# Camera.net
KiCad netlist of a schematic drawn in Altium Designer
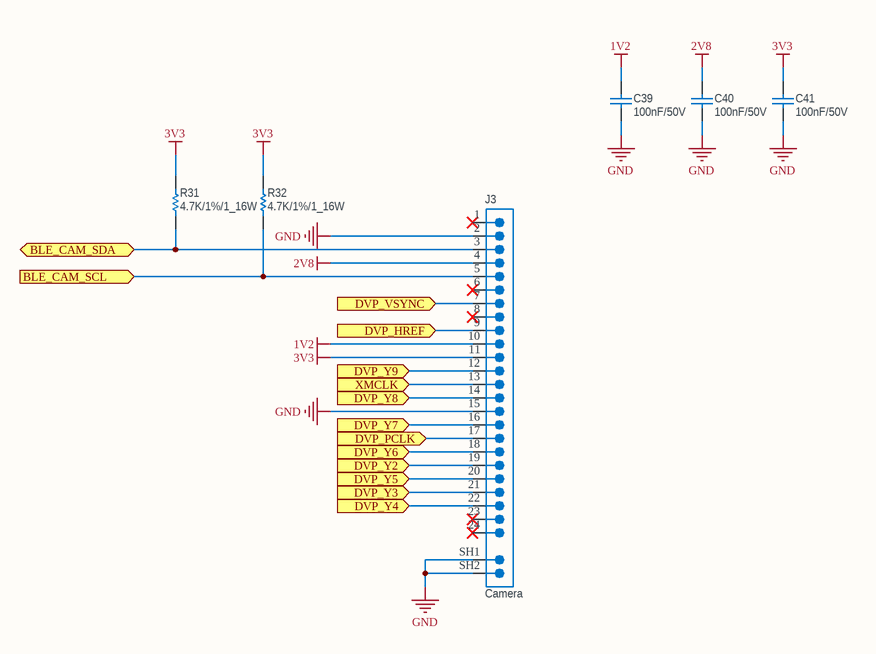
[diagram p0: Camera.SchDoc]

(export (version "E")
  (design (tool "Eeschema 10.0.6"))
  (components
    (comp (ref "C39")
      (value "100nF/50V")
      (footprint "CAP_0402")
      (description "CAP, size 0402, 100nF, 50V")
      (fields (field (name "SUPPLY PART NUMBER") "Tụ Gốm 0402 100nF (0.1uF) 50V"))
      (libsource (lib "BluetoothTracking") (part "Ceramic_Cap_100nF_50V_0402"))
    )
    (comp (ref "C40")
      (value "100nF/50V")
      (footprint "CAP_0402")
      (description "CAP, size 0402, 100nF, 50V")
      (fields (field (name "SUPPLY PART NUMBER") "Tụ Gốm 0402 100nF (0.1uF) 50V"))
      (libsource (lib "BluetoothTracking") (part "Ceramic_Cap_100nF_50V_0402"))
    )
    (comp (ref "C41")
      (value "100nF/50V")
      (footprint "CAP_0402")
      (description "CAP, size 0402, 100nF, 50V")
      (fields (field (name "SUPPLY PART NUMBER") "Tụ Gốm 0402 100nF (0.1uF) 50V"))
      (libsource (lib "BluetoothTracking") (part "Ceramic_Cap_100nF_50V_0402"))
    )
    (comp (ref "J3")
      (value "Camera")
      (footprint "FPC_0.5mm_24P")
      (description "Cổng FPC 24 Chân 0.5mm Tiếp Điểm Trên, 0.4A 50V")
      (fields (field (name "SUPPLY PART NUMBER") "Cổng FPC 24 Chân 0.5mm Tiếp Điểm Trên"))
      (libsource (lib "BluetoothTracking") (part "FPC_0.5mm_24P"))
    )
    (comp (ref "R31")
      (value "4.7K/1%/1_16W")
      (footprint "RESISTOR_0402")
      (description "Resistor 0402 4.7KOhm 1% 1_16W")
      (fields (field (name "SUPPLY PART NUMBER") "Điện Trở 4.7 KOhm 0402 1%"))
      (libsource (lib "BluetoothTracking") (part "Res_4.7K_0402_1%"))
    )
    (comp (ref "R32")
      (value "4.7K/1%/1_16W")
      (footprint "RESISTOR_0402")
      (description "Resistor 0402 4.7KOhm 1% 1_16W")
      (fields (field (name "SUPPLY PART NUMBER") "Điện Trở 4.7 KOhm 0402 1%"))
      (libsource (lib "BluetoothTracking") (part "Res_4.7K_0402_1%"))
    )
  )
  (nets
    (net (code "1") (name "/BLE_CAM_SCL") (class "Default")
      (node (ref "J3") (pin "5") (pinfunction "5_5") (pintype "passive"))
      (node (ref "R32") (pin "1") (pinfunction "1_1") (pintype "passive"))
    )
    (net (code "2") (name "/BLE_CAM_SDA") (class "Default")
      (node (ref "J3") (pin "3") (pinfunction "3_3") (pintype "passive"))
      (node (ref "R31") (pin "1") (pinfunction "1_1") (pintype "passive"))
    )
    (net (code "3") (name "/DVP_HREF") (class "Default")
      (node (ref "J3") (pin "9") (pinfunction "9_9") (pintype "passive"))
    )
    (net (code "4") (name "/DVP_PCLK") (class "Default")
      (node (ref "J3") (pin "17") (pinfunction "17_17") (pintype "passive"))
    )
    (net (code "5") (name "/DVP_VSYNC") (class "Default")
      (node (ref "J3") (pin "7") (pinfunction "7_7") (pintype "passive"))
    )
    (net (code "6") (name "/DVP_Y2") (class "Default")
      (node (ref "J3") (pin "19") (pinfunction "19_19") (pintype "passive"))
    )
    (net (code "7") (name "/DVP_Y3") (class "Default")
      (node (ref "J3") (pin "21") (pinfunction "21_21") (pintype "passive"))
    )
    (net (code "8") (name "/DVP_Y4") (class "Default")
      (node (ref "J3") (pin "22") (pinfunction "22_22") (pintype "passive"))
    )
    (net (code "9") (name "/DVP_Y5") (class "Default")
      (node (ref "J3") (pin "20") (pinfunction "20_20") (pintype "passive"))
    )
    (net (code "10") (name "/DVP_Y6") (class "Default")
      (node (ref "J3") (pin "18") (pinfunction "18_18") (pintype "passive"))
    )
    (net (code "11") (name "/DVP_Y7") (class "Default")
      (node (ref "J3") (pin "16") (pinfunction "16_16") (pintype "passive"))
    )
    (net (code "12") (name "/DVP_Y8") (class "Default")
      (node (ref "J3") (pin "14") (pinfunction "14_14") (pintype "passive"))
    )
    (net (code "13") (name "/DVP_Y9") (class "Default")
      (node (ref "J3") (pin "12") (pinfunction "12_12") (pintype "passive"))
    )
    (net (code "14") (name "/XMCLK") (class "Default")
      (node (ref "J3") (pin "13") (pinfunction "13_13") (pintype "passive"))
    )
    (net (code "15") (name "1V2") (class "Default")
      (node (ref "C39") (pin "2") (pinfunction "2_2") (pintype "passive"))
      (node (ref "J3") (pin "10") (pinfunction "10_10") (pintype "passive"))
    )
    (net (code "16") (name "2V8") (class "Default")
      (node (ref "C40") (pin "2") (pinfunction "2_2") (pintype "passive"))
      (node (ref "J3") (pin "4") (pinfunction "4_4") (pintype "passive"))
    )
    (net (code "17") (name "3V3") (class "Default")
      (node (ref "C41") (pin "2") (pinfunction "2_2") (pintype "passive"))
      (node (ref "J3") (pin "11") (pinfunction "11_11") (pintype "passive"))
      (node (ref "R31") (pin "2") (pinfunction "2_2") (pintype "passive"))
      (node (ref "R32") (pin "2") (pinfunction "2_2") (pintype "passive"))
    )
    (net (code "18") (name "GND") (class "Default")
      (node (ref "C39") (pin "1") (pinfunction "1_1") (pintype "passive"))
      (node (ref "C40") (pin "1") (pinfunction "1_1") (pintype "passive"))
      (node (ref "C41") (pin "1") (pinfunction "1_1") (pintype "passive"))
      (node (ref "J3") (pin "15") (pinfunction "15_15") (pintype "passive"))
      (node (ref "J3") (pin "2") (pinfunction "2_2") (pintype "passive"))
      (node (ref "J3") (pin "SH1") (pinfunction "SHIELD_SH1") (pintype "passive"))
      (node (ref "J3") (pin "SH2") (pinfunction "SHIELD_SH2") (pintype "passive"))
    )
    (net (code "19") (name "unconnected-(J3-Pad1)") (class "Default")
      (node (ref "J3") (pin "1") (pinfunction "1_1") (pintype "passive+no_connect"))
    )
    (net (code "20") (name "unconnected-(J3-Pad6)") (class "Default")
      (node (ref "J3") (pin "6") (pinfunction "6_6") (pintype "passive+no_connect"))
    )
    (net (code "21") (name "unconnected-(J3-Pad8)") (class "Default")
      (node (ref "J3") (pin "8") (pinfunction "8_8") (pintype "passive+no_connect"))
    )
    (net (code "22") (name "unconnected-(J3-Pad23)") (class "Default")
      (node (ref "J3") (pin "23") (pinfunction "23_23") (pintype "passive+no_connect"))
    )
    (net (code "23") (name "unconnected-(J3-Pad24)") (class "Default")
      (node (ref "J3") (pin "24") (pinfunction "24_24") (pintype "passive+no_connect"))
    )
  )
)
